# TemperatureSensor.net
KiCad netlist of a schematic drawn in EAGLE
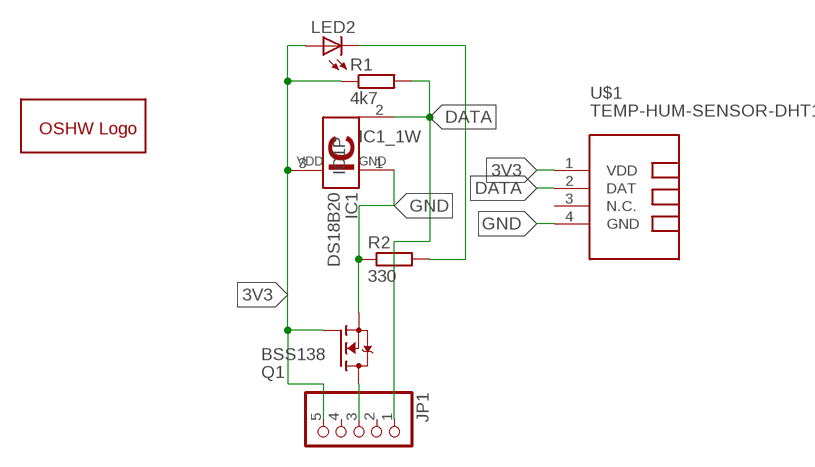
[diagram p0: schematic, sheet 1]

(export (version "E")
  (design (tool "Eeschema 10.0.6"))
  (components
    (comp (ref "IC1")
      (value "DS18B20")
      (footprint "eagle-import:TO92-")
      (libsource (lib "eagle-import") (part "DS18B20"))
    )
    (comp (ref "JP1")
      (value "PINHD-1X5")
      (footprint "eagle-import:1X05")
      (libsource (lib "eagle-import") (part "PINHD-1X5"))
    )
    (comp (ref "LED2")
      (value "LEDSMT1206")
      (footprint "eagle-import:1206")
      (libsource (lib "eagle-import") (part "LEDSMT1206"))
    )
    (comp (ref "Q1")
      (value "BSS138")
      (footprint "eagle-import:SOT23")
      (fields (field (name "MF") "Fairchild"))
      (libsource (lib "eagle-import") (part "BSS138"))
    )
    (comp (ref "R1")
      (value "4k7")
      (footprint "eagle-import:R1206")
      (libsource (lib "eagle-import") (part "R-EU_R1206"))
    )
    (comp (ref "R2")
      (value "330")
      (footprint "eagle-import:R1206")
      (libsource (lib "eagle-import") (part "R-EU_R1206"))
    )
    (comp (ref "U$1")
      (value "TEMP-HUM-SENSOR-DHT11")
      (footprint "eagle-import:TEMP-HUM-SENSOR-DHT11")
      (libsource (lib "eagle-import") (part "TEMP-HUM-SENSOR-DHT11"))
    )
    (comp (ref "U$2")
      (value "OPENSOURCE")
      (footprint "eagle-import:OSHW_5MM")
      (libsource (lib "eagle-import") (part "OPENSOURCE"))
    )
  )
  (nets
    (net (code "1") (name "3V3") (class "Default")
      (node (ref "IC1") (pin "3") (pinfunction "VDD_3") (pintype "power_in"))
      (node (ref "JP1") (pin "5") (pinfunction "5_5") (pintype "passive"))
      (node (ref "LED2") (pin "A") (pinfunction "A_A") (pintype "passive"))
      (node (ref "Q1") (pin "1") (pinfunction "G_1") (pintype "passive"))
      (node (ref "R1") (pin "1") (pinfunction "1_1") (pintype "passive"))
      (node (ref "U$1") (pin "1") (pinfunction "VDD_1") (pintype "power_in"))
    )
    (net (code "2") (name "DATA") (class "Default")
      (node (ref "IC1") (pin "2") (pinfunction "1W_2") (pintype "power_in"))
      (node (ref "JP1") (pin "1") (pinfunction "1_1") (pintype "passive"))
      (node (ref "R1") (pin "2") (pinfunction "2_2") (pintype "passive"))
      (node (ref "U$1") (pin "2") (pinfunction "DAT_2") (pintype "bidirectional"))
    )
    (net (code "3") (name "GND") (class "Default")
      (node (ref "IC1") (pin "1") (pinfunction "GND_1") (pintype "power_in"))
      (node (ref "Q1") (pin "2") (pinfunction "S_2") (pintype "passive"))
      (node (ref "R2") (pin "1") (pinfunction "1_1") (pintype "passive"))
      (node (ref "U$1") (pin "4") (pinfunction "GND_4") (pintype "power_in"))
    )
    (net (code "4") (name "Net-(LED2-PadC)") (class "Default")
      (node (ref "LED2") (pin "C") (pinfunction "C_C") (pintype "passive"))
      (node (ref "R2") (pin "2") (pinfunction "2_2") (pintype "passive"))
    )
    (net (code "5") (name "Net-(Q1-D)") (class "Default")
      (node (ref "JP1") (pin "3") (pinfunction "3_3") (pintype "passive"))
      (node (ref "Q1") (pin "3") (pinfunction "D_3") (pintype "passive"))
    )
    (net (code "6") (name "unconnected-(JP1-Pad2)") (class "Default")
      (node (ref "JP1") (pin "2") (pinfunction "2_2") (pintype "passive"))
    )
    (net (code "7") (name "unconnected-(JP1-Pad4)") (class "Default")
      (node (ref "JP1") (pin "4") (pinfunction "4_4") (pintype "passive"))
    )
    (net (code "8") (name "unconnected-(U$1-N.C.-Pad3)") (class "Default")
      (node (ref "U$1") (pin "3") (pinfunction "N.C._3") (pintype "passive"))
    )
  )
)
